# CH1.net
KiCad netlist of a schematic drawn in EAGLE
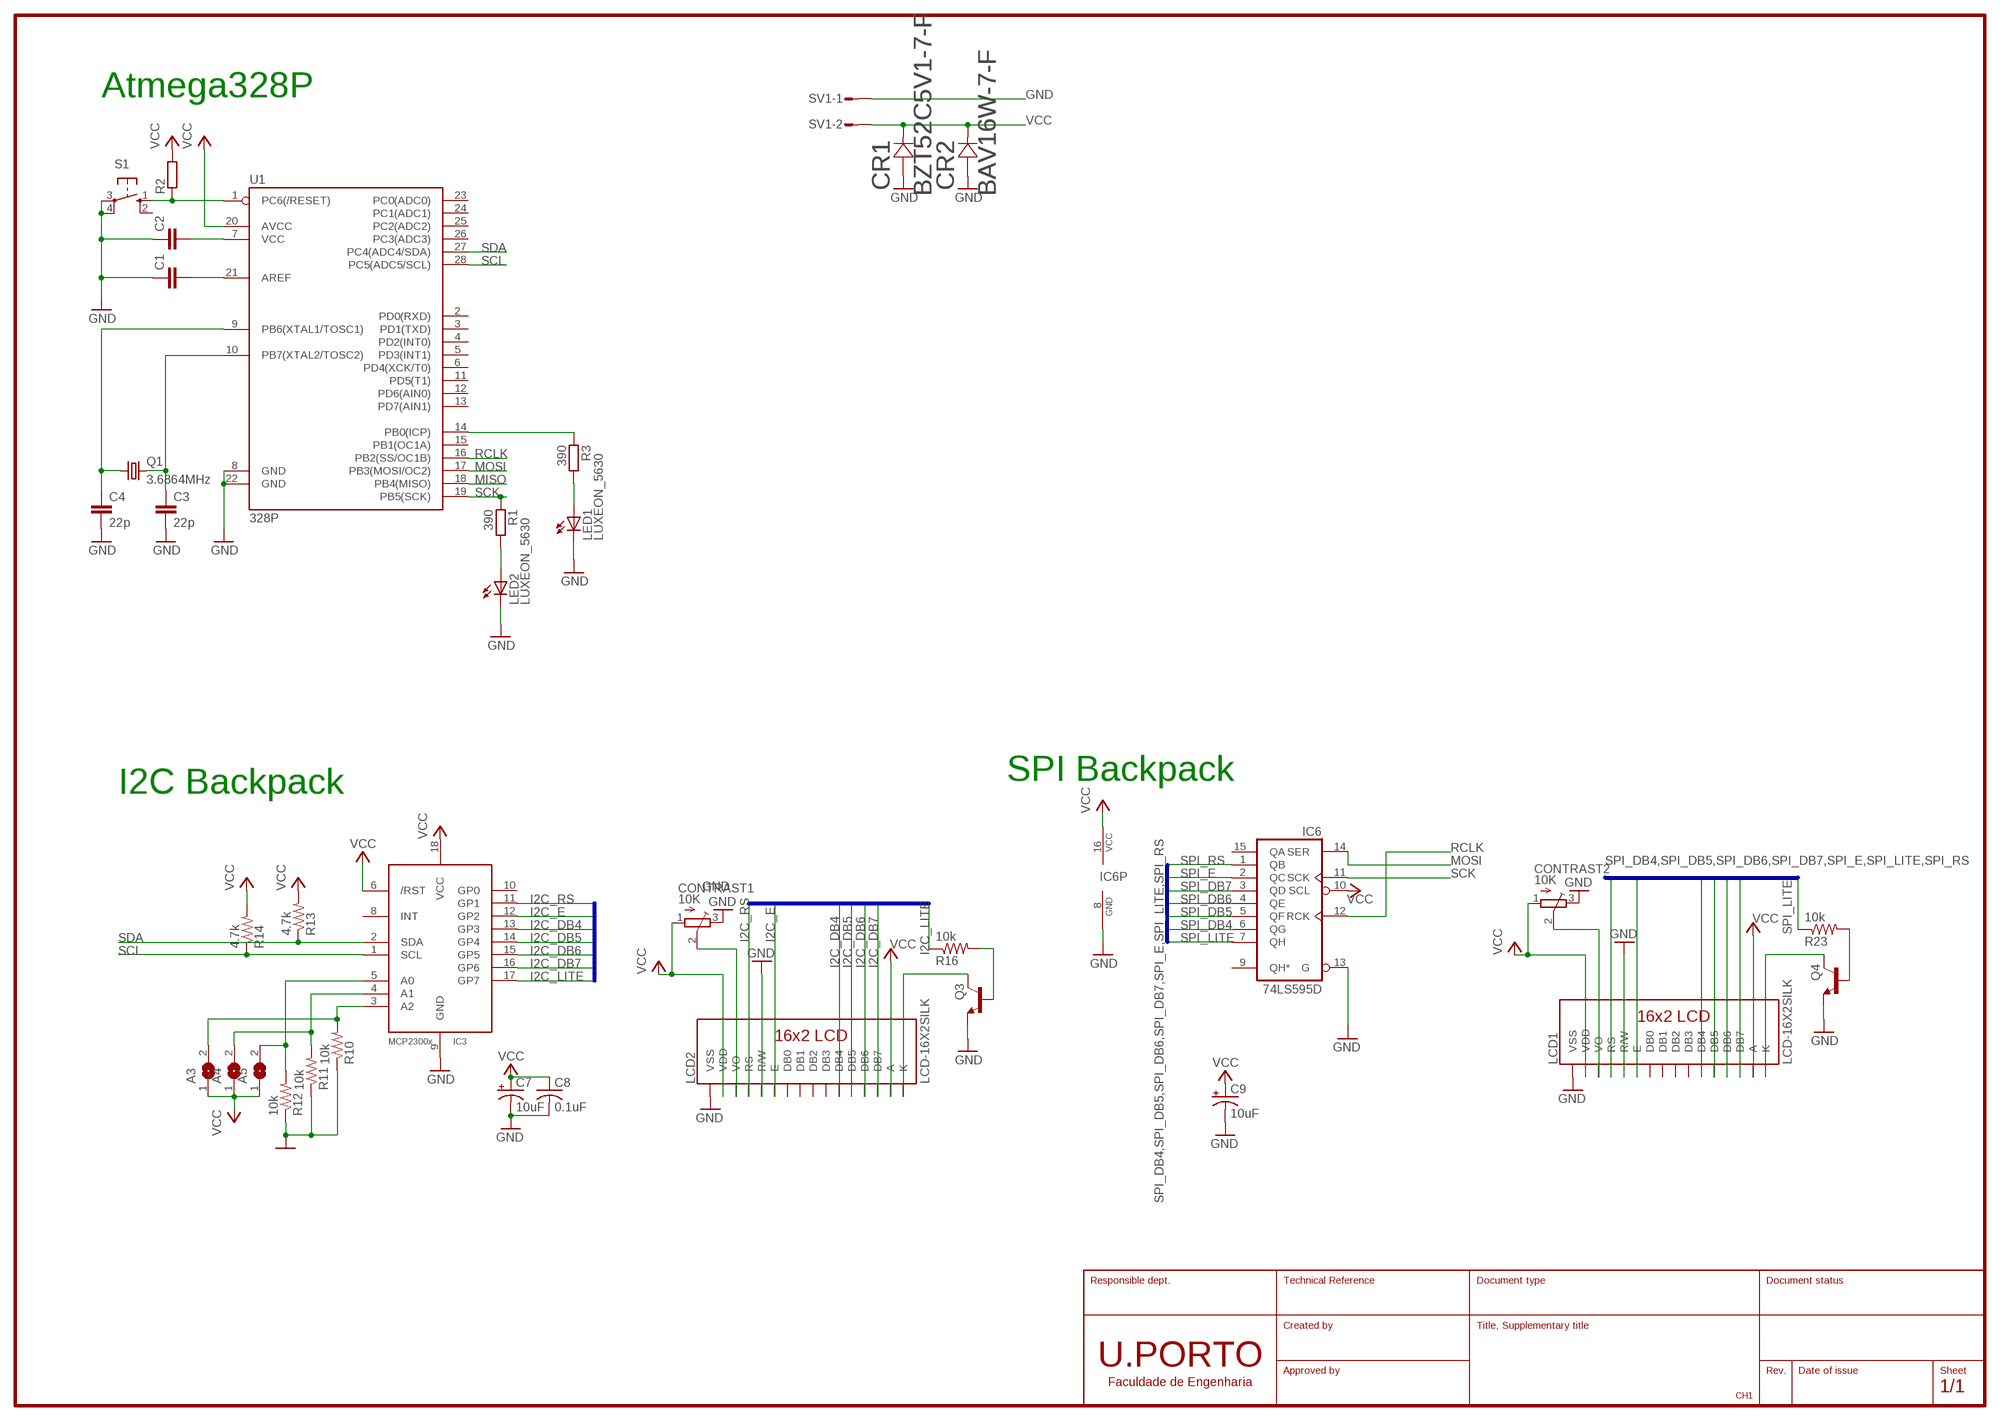
[diagram p0: schematic, sheet 1]

(export (version "E")
  (design (tool "Eeschema 10.0.6"))
  (components
    (comp (ref "A3") (value "SJ") (footprint "eagle-import:SJ") (libsource (lib "eagle-import") (part "SJ")))
    (comp (ref "A4") (value "SJ") (footprint "eagle-import:SJ") (libsource (lib "eagle-import") (part "SJ")))
    (comp (ref "A5") (value "SJ") (footprint "eagle-import:SJ") (libsource (lib "eagle-import") (part "SJ")))
    (comp (ref "C1")
      (value "C-EUC1206")
      (footprint "eagle-import:C1206")
      (libsource (lib "eagle-import") (part "C-EUC1206"))
    )
    (comp (ref "C2")
      (value "C-EUC1206")
      (footprint "eagle-import:C1206")
      (libsource (lib "eagle-import") (part "C-EUC1206"))
    )
    (comp (ref "C3")
      (value "22p")
      (footprint "eagle-import:C1206")
      (libsource (lib "eagle-import") (part "C-EUC1206"))
    )
    (comp (ref "C4")
      (value "22p")
      (footprint "eagle-import:C1206")
      (libsource (lib "eagle-import") (part "C-EUC1206"))
    )
    (comp (ref "C7")
      (value "10uF")
      (footprint "eagle-import:A_3216-18R")
      (libsource (lib "eagle-import") (part "CPOL-USA/3216-18R"))
    )
    (comp (ref "C8")
      (value "0.1uF")
      (footprint "eagle-import:C0805K")
      (libsource (lib "eagle-import") (part "C-USC0805K"))
    )
    (comp (ref "C9")
      (value "10uF")
      (footprint "eagle-import:A_3216-18R")
      (libsource (lib "eagle-import") (part "CPOL-USA/3216-18R"))
    )
    (comp (ref "CONTRAST1")
      (value "10K")
      (footprint "eagle-import:TC33X")
      (libsource (lib "eagle-import") (part "TRIMPOTTC33X"))
    )
    (comp (ref "CONTRAST2")
      (value "10K")
      (footprint "eagle-import:TC33X")
      (libsource (lib "eagle-import") (part "TRIMPOTTC33X"))
    )
    (comp (ref "CR1")
      (value "BZT52C5V1-7-F")
      (footprint "eagle-import:SOD123")
      (fields (field (name "MANUFACTURER_PART_NUMBER") "BZT52C5V17F"))
      (libsource (lib "eagle-import") (part "BZT52C5V1-7-F"))
    )
    (comp (ref "CR2")
      (value "BAV16W-7-F")
      (footprint "eagle-import:SOD123")
      (fields (field (name "MANUFACTURER_PART_NUMBER") "BAV16W7F"))
      (libsource (lib "eagle-import") (part "BAV16W-7-F"))
    )
    (comp (ref "IC3")
      (value "MCP2300X/SO")
      (footprint "eagle-import:SO18W")
      (libsource (lib "eagle-import") (part "MCP2300X/SO"))
    )
    (comp (ref "IC6")
      (value "74LS595D")
      (footprint "eagle-import:SO16")
      (libsource (lib "eagle-import") (part "74595DLS"))
    )
    (comp (ref "LCD1")
      (value "LCD-16X2SILK")
      (footprint "eagle-import:LCD-16X2")
      (libsource (lib "eagle-import") (part "LCD-16X2SILK"))
    )
    (comp (ref "LCD2")
      (value "LCD-16X2SILK")
      (footprint "eagle-import:LCD-16X2")
      (libsource (lib "eagle-import") (part "LCD-16X2SILK"))
    )
    (comp (ref "LED1")
      (value "LUXEON_5630")
      (footprint "eagle-import:LUXEON_5630")
      (libsource (lib "eagle-import") (part "LUXEON_5630"))
    )
    (comp (ref "LED2")
      (value "LUXEON_5630")
      (footprint "eagle-import:LUXEON_5630")
      (libsource (lib "eagle-import") (part "LUXEON_5630"))
    )
    (comp (ref "Q1")
      (value "3.6864MHz")
      (footprint "eagle-import:HC49_S")
      (libsource (lib "eagle-import") (part "CRYSTALHC49S"))
    )
    (comp (ref "Q3")
      (value "MMBT2222ALT1-NPN-SOT23-BEC")
      (footprint "eagle-import:SOT23-BEC")
      (libsource (lib "eagle-import") (part "-NPN-SOT23-BECMMBT2222ALT1"))
    )
    (comp (ref "Q4")
      (value "MMBT2222ALT1-NPN-SOT23-BEC")
      (footprint "eagle-import:SOT23-BEC")
      (libsource (lib "eagle-import") (part "-NPN-SOT23-BECMMBT2222ALT1"))
    )
    (comp (ref "R1")
      (value "390")
      (footprint "eagle-import:R1206")
      (libsource (lib "eagle-import") (part "R-EU_R1206"))
    )
    (comp (ref "R2")
      (value "R-EU_R1206")
      (footprint "eagle-import:R1206")
      (libsource (lib "eagle-import") (part "R-EU_R1206"))
    )
    (comp (ref "R3")
      (value "390")
      (footprint "eagle-import:R1206")
      (libsource (lib "eagle-import") (part "R-EU_R1206"))
    )
    (comp (ref "R10")
      (value "10k")
      (footprint "eagle-import:R0805")
      (libsource (lib "eagle-import") (part "R-US_R0805"))
    )
    (comp (ref "R11")
      (value "10k")
      (footprint "eagle-import:R0805")
      (libsource (lib "eagle-import") (part "R-US_R0805"))
    )
    (comp (ref "R12")
      (value "10k")
      (footprint "eagle-import:R0805")
      (libsource (lib "eagle-import") (part "R-US_R0805"))
    )
    (comp (ref "R13")
      (value "4.7k")
      (footprint "eagle-import:R0805")
      (libsource (lib "eagle-import") (part "R-US_R0805"))
    )
    (comp (ref "R14")
      (value "4.7k")
      (footprint "eagle-import:R0805")
      (libsource (lib "eagle-import") (part "R-US_R0805"))
    )
    (comp (ref "R16")
      (value "10k")
      (footprint "eagle-import:R0805")
      (libsource (lib "eagle-import") (part "R-US_R0805"))
    )
    (comp (ref "R23")
      (value "10k")
      (footprint "eagle-import:R0805")
      (libsource (lib "eagle-import") (part "R-US_R0805"))
    )
    (comp (ref "S1")
      (value "SWITCH-OMRON")
      (footprint "eagle-import:SWITCH-OMRON_B3F-10XX")
      (fields (field (name "MPN") "B3F-1000"))
      (libsource (lib "eagle-import") (part "SWITCH-OMRON"))
    )
    (comp (ref "SV1")
      (value "L02P")
      (footprint "eagle-import:L02P")
      (libsource (lib "eagle-import") (part "L02P"))
    )
    (comp (ref "U1")
      (value "328P")
      (footprint "eagle-import:MICROCONTROLLER_DIP28")
      (libsource (lib "eagle-import") (part "ATMEGA328P-PDIP"))
    )
  )
  (nets
    (net (code "1") (name "/I2C_DB4") (class "Default")
      (node (ref "IC3") (pin "13") (pinfunction "GP3_13") (pintype "bidirectional"))
      (node (ref "LCD2") (pin "11") (pinfunction "DB4_11") (pintype "bidirectional"))
    )
    (net (code "2") (name "/I2C_DB5") (class "Default")
      (node (ref "IC3") (pin "14") (pinfunction "GP4_14") (pintype "bidirectional"))
      (node (ref "LCD2") (pin "12") (pinfunction "DB5_12") (pintype "bidirectional"))
    )
    (net (code "3") (name "/I2C_DB6") (class "Default")
      (node (ref "IC3") (pin "15") (pinfunction "GP5_15") (pintype "bidirectional"))
      (node (ref "LCD2") (pin "13") (pinfunction "DB6_13") (pintype "bidirectional"))
    )
    (net (code "4") (name "/I2C_DB7") (class "Default")
      (node (ref "IC3") (pin "16") (pinfunction "GP6_16") (pintype "bidirectional"))
      (node (ref "LCD2") (pin "14") (pinfunction "DB7_14") (pintype "bidirectional"))
    )
    (net (code "5") (name "/I2C_E") (class "Default")
      (node (ref "IC3") (pin "12") (pinfunction "GP2_12") (pintype "bidirectional"))
      (node (ref "LCD2") (pin "6") (pinfunction "E_6") (pintype "input"))
    )
    (net (code "6") (name "/I2C_LITE") (class "Default")
      (node (ref "IC3") (pin "17") (pinfunction "GP7_17") (pintype "bidirectional"))
      (node (ref "R16") (pin "1") (pinfunction "1_1") (pintype "passive"))
    )
    (net (code "7") (name "/I2C_RS") (class "Default")
      (node (ref "IC3") (pin "11") (pinfunction "GP1_11") (pintype "bidirectional"))
      (node (ref "LCD2") (pin "4") (pinfunction "RS_4") (pintype "input"))
    )
    (net (code "8") (name "/MISO") (class "Default")
      (node (ref "U1") (pin "18") (pinfunction "PB4(MISO)_18") (pintype "bidirectional"))
    )
    (net (code "9") (name "/MOSI") (class "Default")
      (node (ref "IC6") (pin "14") (pinfunction "SER_14") (pintype "input"))
      (node (ref "U1") (pin "17") (pinfunction "PB3(MOSI/OC2)_17") (pintype "bidirectional"))
    )
    (net (code "10") (name "/RCLK") (class "Default")
      (node (ref "IC6") (pin "12") (pinfunction "RCK_12") (pintype "input"))
      (node (ref "U1") (pin "16") (pinfunction "PB2(SS/OC1B)_16") (pintype "bidirectional"))
    )
    (net (code "11") (name "/SCK") (class "Default")
      (node (ref "IC6") (pin "11") (pinfunction "SCK_11") (pintype "input"))
      (node (ref "R1") (pin "1") (pinfunction "1_1") (pintype "passive"))
      (node (ref "U1") (pin "19") (pinfunction "PB5(SCK)_19") (pintype "bidirectional"))
    )
    (net (code "12") (name "/SCL") (class "Default")
      (node (ref "IC3") (pin "1") (pinfunction "SCL_1") (pintype "bidirectional"))
      (node (ref "R14") (pin "1") (pinfunction "1_1") (pintype "passive"))
      (node (ref "U1") (pin "28") (pinfunction "PC5(ADC5/SCL)_28") (pintype "bidirectional"))
    )
    (net (code "13") (name "/SDA") (class "Default")
      (node (ref "IC3") (pin "2") (pinfunction "SDA_2") (pintype "bidirectional"))
      (node (ref "R13") (pin "1") (pinfunction "1_1") (pintype "passive"))
      (node (ref "U1") (pin "27") (pinfunction "PC4(ADC4/SDA)_27") (pintype "bidirectional"))
    )
    (net (code "14") (name "/SPI_DB4") (class "Default")
      (node (ref "IC6") (pin "6") (pinfunction "QG_6") (pintype "tri_state"))
      (node (ref "LCD1") (pin "11") (pinfunction "DB4_11") (pintype "bidirectional"))
    )
    (net (code "15") (name "/SPI_DB5") (class "Default")
      (node (ref "IC6") (pin "5") (pinfunction "QF_5") (pintype "tri_state"))
      (node (ref "LCD1") (pin "12") (pinfunction "DB5_12") (pintype "bidirectional"))
    )
    (net (code "16") (name "/SPI_DB6") (class "Default")
      (node (ref "IC6") (pin "4") (pinfunction "QE_4") (pintype "tri_state"))
      (node (ref "LCD1") (pin "13") (pinfunction "DB6_13") (pintype "bidirectional"))
    )
    (net (code "17") (name "/SPI_DB7") (class "Default")
      (node (ref "IC6") (pin "3") (pinfunction "QD_3") (pintype "tri_state"))
      (node (ref "LCD1") (pin "14") (pinfunction "DB7_14") (pintype "bidirectional"))
    )
    (net (code "18") (name "/SPI_E") (class "Default")
      (node (ref "IC6") (pin "2") (pinfunction "QC_2") (pintype "tri_state"))
      (node (ref "LCD1") (pin "6") (pinfunction "E_6") (pintype "input"))
    )
    (net (code "19") (name "/SPI_LITE") (class "Default")
      (node (ref "IC6") (pin "7") (pinfunction "QH_7") (pintype "tri_state"))
      (node (ref "R23") (pin "1") (pinfunction "1_1") (pintype "passive"))
    )
    (net (code "20") (name "/SPI_RS") (class "Default")
      (node (ref "IC6") (pin "1") (pinfunction "QB_1") (pintype "tri_state"))
      (node (ref "LCD1") (pin "4") (pinfunction "RS_4") (pintype "input"))
    )
    (net (code "22") (name "GND") (class "Default")
      (node (ref "C1") (pin "1") (pinfunction "1_1") (pintype "passive"))
      (node (ref "C2") (pin "1") (pinfunction "1_1") (pintype "passive"))
      (node (ref "C3") (pin "2") (pinfunction "2_2") (pintype "passive"))
      (node (ref "C4") (pin "2") (pinfunction "2_2") (pintype "passive"))
      (node (ref "C7") (pin "-") (pinfunction "-_-") (pintype "passive"))
      (node (ref "C8") (pin "2") (pinfunction "2_2") (pintype "passive"))
      (node (ref "C9") (pin "-") (pinfunction "-_-") (pintype "passive"))
      (node (ref "CONTRAST1") (pin "3") (pinfunction "E_3") (pintype "passive"))
      (node (ref "CONTRAST2") (pin "3") (pinfunction "E_3") (pintype "passive"))
      (node (ref "CR1") (pin "2") (pinfunction "21_2") (pintype "passive"))
      (node (ref "CR2") (pin "2") (pinfunction "21_2") (pintype "passive"))
      (node (ref "IC3") (pin "9") (pinfunction "GND_9") (pintype "power_in"))
      (node (ref "IC6") (pin "13") (pinfunction "G_13") (pintype "input"))
      (node (ref "IC6") (pin "8") (pinfunction "GND_8") (pintype "power_in"))
      (node (ref "LCD1") (pin "1") (pinfunction "VSS_1") (pintype "power_in"))
      (node (ref "LCD1") (pin "5") (pinfunction "R/W_5") (pintype "input"))
      (node (ref "LCD2") (pin "1") (pinfunction "VSS_1") (pintype "power_in"))
      (node (ref "LCD2") (pin "5") (pinfunction "R/W_5") (pintype "input"))
      (node (ref "LED1") (pin "1@1") (pinfunction "C_1@1") (pintype "passive"))
      (node (ref "LED1") (pin "1@2") (pinfunction "C_1@2") (pintype "passive"))
      (node (ref "LED2") (pin "1@1") (pinfunction "C_1@1") (pintype "passive"))
      (node (ref "LED2") (pin "1@2") (pinfunction "C_1@2") (pintype "passive"))
      (node (ref "Q3") (pin "E") (pinfunction "E_E") (pintype "passive"))
      (node (ref "Q4") (pin "E") (pinfunction "E_E") (pintype "passive"))
      (node (ref "R10") (pin "1") (pinfunction "1_1") (pintype "passive"))
      (node (ref "R11") (pin "1") (pinfunction "1_1") (pintype "passive"))
      (node (ref "R12") (pin "1") (pinfunction "1_1") (pintype "passive"))
      (node (ref "S1") (pin "3") (pinfunction "P_3") (pintype "passive"))
      (node (ref "S1") (pin "4") (pinfunction "P1_4") (pintype "passive"))
      (node (ref "SV1") (pin "1") (pinfunction "S_1") (pintype "passive"))
      (node (ref "U1") (pin "22") (pinfunction "GND_22") (pintype "bidirectional"))
      (node (ref "U1") (pin "8") (pinfunction "GND_8") (pintype "bidirectional"))
    )
    (net (code "23") (name "Net-(CONTRAST1-S)") (class "Default")
      (node (ref "CONTRAST1") (pin "2") (pinfunction "S_2") (pintype "passive"))
      (node (ref "LCD2") (pin "3") (pinfunction "VO_3") (pintype "bidirectional"))
    )
    (net (code "24") (name "Net-(CONTRAST2-S)") (class "Default")
      (node (ref "CONTRAST2") (pin "2") (pinfunction "S_2") (pintype "passive"))
      (node (ref "LCD1") (pin "3") (pinfunction "VO_3") (pintype "bidirectional"))
    )
    (net (code "25") (name "Net-(IC3-A0)") (class "Default")
      (node (ref "A5") (pin "2") (pinfunction "2_2") (pintype "passive"))
      (node (ref "IC3") (pin "5") (pinfunction "A0_5") (pintype "input"))
      (node (ref "R12") (pin "2") (pinfunction "2_2") (pintype "passive"))
    )
    (net (code "26") (name "Net-(IC3-A1)") (class "Default")
      (node (ref "A4") (pin "2") (pinfunction "2_2") (pintype "passive"))
      (node (ref "IC3") (pin "4") (pinfunction "A1_4") (pintype "input"))
      (node (ref "R11") (pin "2") (pinfunction "2_2") (pintype "passive"))
    )
    (net (code "27") (name "Net-(IC3-A2)") (class "Default")
      (node (ref "A3") (pin "2") (pinfunction "2_2") (pintype "passive"))
      (node (ref "IC3") (pin "3") (pinfunction "A2_3") (pintype "input"))
      (node (ref "R10") (pin "2") (pinfunction "2_2") (pintype "passive"))
    )
    (net (code "28") (name "Net-(LCD1-K)") (class "Default")
      (node (ref "LCD1") (pin "16") (pinfunction "K_16") (pintype "power_in"))
      (node (ref "Q4") (pin "C") (pinfunction "C_C") (pintype "passive"))
    )
    (net (code "29") (name "Net-(LCD2-K)") (class "Default")
      (node (ref "LCD2") (pin "16") (pinfunction "K_16") (pintype "power_in"))
      (node (ref "Q3") (pin "C") (pinfunction "C_C") (pintype "passive"))
    )
    (net (code "30") (name "Net-(LED1-A)") (class "Default")
      (node (ref "LED1") (pin "2") (pinfunction "A_2") (pintype "passive"))
      (node (ref "R3") (pin "2") (pinfunction "2_2") (pintype "passive"))
    )
    (net (code "31") (name "Net-(LED2-A)") (class "Default")
      (node (ref "LED2") (pin "2") (pinfunction "A_2") (pintype "passive"))
      (node (ref "R1") (pin "2") (pinfunction "2_2") (pintype "passive"))
    )
    (net (code "32") (name "Net-(Q3-PadB)") (class "Default")
      (node (ref "Q3") (pin "B") (pinfunction "B_B") (pintype "passive"))
      (node (ref "R16") (pin "2") (pinfunction "2_2") (pintype "passive"))
    )
    (net (code "33") (name "Net-(Q4-PadB)") (class "Default")
      (node (ref "Q4") (pin "B") (pinfunction "B_B") (pintype "passive"))
      (node (ref "R23") (pin "2") (pinfunction "2_2") (pintype "passive"))
    )
    (net (code "34") (name "Net-(S1-S)") (class "Default")
      (node (ref "R2") (pin "1") (pinfunction "1_1") (pintype "passive"))
      (node (ref "S1") (pin "1") (pinfunction "S_1") (pintype "passive"))
      (node (ref "U1") (pin "1") (pinfunction "PC6(/RESET)_1") (pintype "bidirectional"))
    )
    (net (code "35") (name "Net-(U1-AREF)") (class "Default")
      (node (ref "C1") (pin "2") (pinfunction "2_2") (pintype "passive"))
      (node (ref "U1") (pin "21") (pinfunction "AREF_21") (pintype "bidirectional"))
    )
    (net (code "36") (name "Net-(U1-PB0(ICP))") (class "Default")
      (node (ref "R3") (pin "1") (pinfunction "1_1") (pintype "passive"))
      (node (ref "U1") (pin "14") (pinfunction "PB0(ICP)_14") (pintype "bidirectional"))
    )
    (net (code "37") (name "Net-(U1-PB6(XTAL1{slash}TOSC1))") (class "Default")
      (node (ref "C4") (pin "1") (pinfunction "1_1") (pintype "passive"))
      (node (ref "Q1") (pin "1") (pinfunction "1_1") (pintype "passive"))
      (node (ref "U1") (pin "9") (pinfunction "PB6(XTAL1/TOSC1)_9") (pintype "bidirectional"))
    )
    (net (code "38") (name "Net-(U1-PB7(XTAL2{slash}TOSC2))") (class "Default")
      (node (ref "C3") (pin "1") (pinfunction "1_1") (pintype "passive"))
      (node (ref "Q1") (pin "2") (pinfunction "2_2") (pintype "passive"))
      (node (ref "U1") (pin "10") (pinfunction "PB7(XTAL2/TOSC2)_10") (pintype "bidirectional"))
    )
    (net (code "39") (name "Net-(U1-VCC)") (class "Default")
      (node (ref "C2") (pin "2") (pinfunction "2_2") (pintype "passive"))
      (node (ref "U1") (pin "7") (pinfunction "VCC_7") (pintype "bidirectional"))
    )
    (net (code "40") (name "VCC") (class "Default")
      (node (ref "A3") (pin "1") (pinfunction "1_1") (pintype "passive"))
      (node (ref "A4") (pin "1") (pinfunction "1_1") (pintype "passive"))
      (node (ref "A5") (pin "1") (pinfunction "1_1") (pintype "passive"))
      (node (ref "C7") (pin "+") (pinfunction "+_+") (pintype "passive"))
      (node (ref "C8") (pin "1") (pinfunction "1_1") (pintype "passive"))
      (node (ref "C9") (pin "+") (pinfunction "+_+") (pintype "passive"))
      (node (ref "CONTRAST1") (pin "1") (pinfunction "A_1") (pintype "passive"))
      (node (ref "CONTRAST2") (pin "1") (pinfunction "A_1") (pintype "passive"))
      (node (ref "CR1") (pin "1") (pinfunction "12_1") (pintype "passive"))
      (node (ref "CR2") (pin "1") (pinfunction "12_1") (pintype "passive"))
      (node (ref "IC3") (pin "18") (pinfunction "VCC_18") (pintype "power_in"))
      (node (ref "IC3") (pin "6") (pinfunction "/RST_6") (pintype "input"))
      (node (ref "IC6") (pin "10") (pinfunction "SCL_10") (pintype "input"))
      (node (ref "IC6") (pin "16") (pinfunction "VCC_16") (pintype "power_in"))
      (node (ref "LCD1") (pin "15") (pinfunction "A_15") (pintype "power_in"))
      (node (ref "LCD1") (pin "2") (pinfunction "VDD_2") (pintype "power_in"))
      (node (ref "LCD2") (pin "15") (pinfunction "A_15") (pintype "power_in"))
      (node (ref "LCD2") (pin "2") (pinfunction "VDD_2") (pintype "power_in"))
      (node (ref "R13") (pin "2") (pinfunction "2_2") (pintype "passive"))
      (node (ref "R14") (pin "2") (pinfunction "2_2") (pintype "passive"))
      (node (ref "R2") (pin "2") (pinfunction "2_2") (pintype "passive"))
      (node (ref "SV1") (pin "2") (pinfunction "S_2") (pintype "passive"))
      (node (ref "U1") (pin "20") (pinfunction "AVCC_20") (pintype "bidirectional"))
    )
    (net (code "41") (name "unconnected-(IC3-GP0-Pad10)") (class "Default")
      (node (ref "IC3") (pin "10") (pinfunction "GP0_10") (pintype "bidirectional"))
    )
    (net (code "42") (name "unconnected-(IC3-INT-Pad8)") (class "Default")
      (node (ref "IC3") (pin "8") (pinfunction "INT_8") (pintype "output"))
    )
    (net (code "43") (name "unconnected-(IC6A-QA-Pad15)") (class "Default")
      (node (ref "IC6") (pin "15") (pinfunction "QA_15") (pintype "tri_state"))
    )
    (net (code "44") (name "unconnected-(IC6A-QH*-Pad9)") (class "Default")
      (node (ref "IC6") (pin "9") (pinfunction "QH*_9") (pintype "tri_state"))
    )
    (net (code "45") (name "unconnected-(LCD1-DB0-Pad7)") (class "Default")
      (node (ref "LCD1") (pin "7") (pinfunction "DB0_7") (pintype "bidirectional"))
    )
    (net (code "46") (name "unconnected-(LCD1-DB1-Pad8)") (class "Default")
      (node (ref "LCD1") (pin "8") (pinfunction "DB1_8") (pintype "bidirectional"))
    )
    (net (code "47") (name "unconnected-(LCD1-DB2-Pad9)") (class "Default")
      (node (ref "LCD1") (pin "9") (pinfunction "DB2_9") (pintype "bidirectional"))
    )
    (net (code "48") (name "unconnected-(LCD1-DB3-Pad10)") (class "Default")
      (node (ref "LCD1") (pin "10") (pinfunction "DB3_10") (pintype "bidirectional"))
    )
    (net (code "49") (name "unconnected-(LCD2-DB0-Pad7)") (class "Default")
      (node (ref "LCD2") (pin "7") (pinfunction "DB0_7") (pintype "bidirectional"))
    )
    (net (code "50") (name "unconnected-(LCD2-DB1-Pad8)") (class "Default")
      (node (ref "LCD2") (pin "8") (pinfunction "DB1_8") (pintype "bidirectional"))
    )
    (net (code "51") (name "unconnected-(LCD2-DB2-Pad9)") (class "Default")
      (node (ref "LCD2") (pin "9") (pinfunction "DB2_9") (pintype "bidirectional"))
    )
    (net (code "52") (name "unconnected-(LCD2-DB3-Pad10)") (class "Default")
      (node (ref "LCD2") (pin "10") (pinfunction "DB3_10") (pintype "bidirectional"))
    )
    (net (code "53") (name "unconnected-(S1-S1-Pad2)") (class "Default")
      (node (ref "S1") (pin "2") (pinfunction "S1_2") (pintype "passive"))
    )
    (net (code "54") (name "unconnected-(U1-PB1(OC1A)-Pad15)") (class "Default")
      (node (ref "U1") (pin "15") (pinfunction "PB1(OC1A)_15") (pintype "bidirectional"))
    )
    (net (code "55") (name "unconnected-(U1-PC0(ADC0)-Pad23)") (class "Default")
      (node (ref "U1") (pin "23") (pinfunction "PC0(ADC0)_23") (pintype "bidirectional"))
    )
    (net (code "56") (name "unconnected-(U1-PC1(ADC1)-Pad24)") (class "Default")
      (node (ref "U1") (pin "24") (pinfunction "PC1(ADC1)_24") (pintype "bidirectional"))
    )
    (net (code "57") (name "unconnected-(U1-PC2(ADC2)-Pad25)") (class "Default")
      (node (ref "U1") (pin "25") (pinfunction "PC2(ADC2)_25") (pintype "bidirectional"))
    )
    (net (code "58") (name "unconnected-(U1-PC3(ADC3)-Pad26)") (class "Default")
      (node (ref "U1") (pin "26") (pinfunction "PC3(ADC3)_26") (pintype "bidirectional"))
    )
    (net (code "59") (name "unconnected-(U1-PD0(RXD)-Pad2)") (class "Default")
      (node (ref "U1") (pin "2") (pinfunction "PD0(RXD)_2") (pintype "bidirectional"))
    )
    (net (code "60") (name "unconnected-(U1-PD1(TXD)-Pad3)") (class "Default")
      (node (ref "U1") (pin "3") (pinfunction "PD1(TXD)_3") (pintype "bidirectional"))
    )
    (net (code "61") (name "unconnected-(U1-PD2(INT0)-Pad4)") (class "Default")
      (node (ref "U1") (pin "4") (pinfunction "PD2(INT0)_4") (pintype "bidirectional"))
    )
    (net (code "62") (name "unconnected-(U1-PD3(INT1)-Pad5)") (class "Default")
      (node (ref "U1") (pin "5") (pinfunction "PD3(INT1)_5") (pintype "bidirectional"))
    )
    (net (code "63") (name "unconnected-(U1-PD4(XCK{slash}T0)-Pad6)") (class "Default")
      (node (ref "U1") (pin "6") (pinfunction "PD4(XCK/T0)_6") (pintype "bidirectional"))
    )
    (net (code "64") (name "unconnected-(U1-PD5(T1)-Pad11)") (class "Default")
      (node (ref "U1") (pin "11") (pinfunction "PD5(T1)_11") (pintype "bidirectional"))
    )
    (net (code "65") (name "unconnected-(U1-PD6(AIN0)-Pad12)") (class "Default")
      (node (ref "U1") (pin "12") (pinfunction "PD6(AIN0)_12") (pintype "bidirectional"))
    )
    (net (code "66") (name "unconnected-(U1-PD7(AIN1)-Pad13)") (class "Default")
      (node (ref "U1") (pin "13") (pinfunction "PD7(AIN1)_13") (pintype "bidirectional"))
    )
  )
)
